# stm32-40.net
KiCad netlist of a schematic drawn in EAGLE
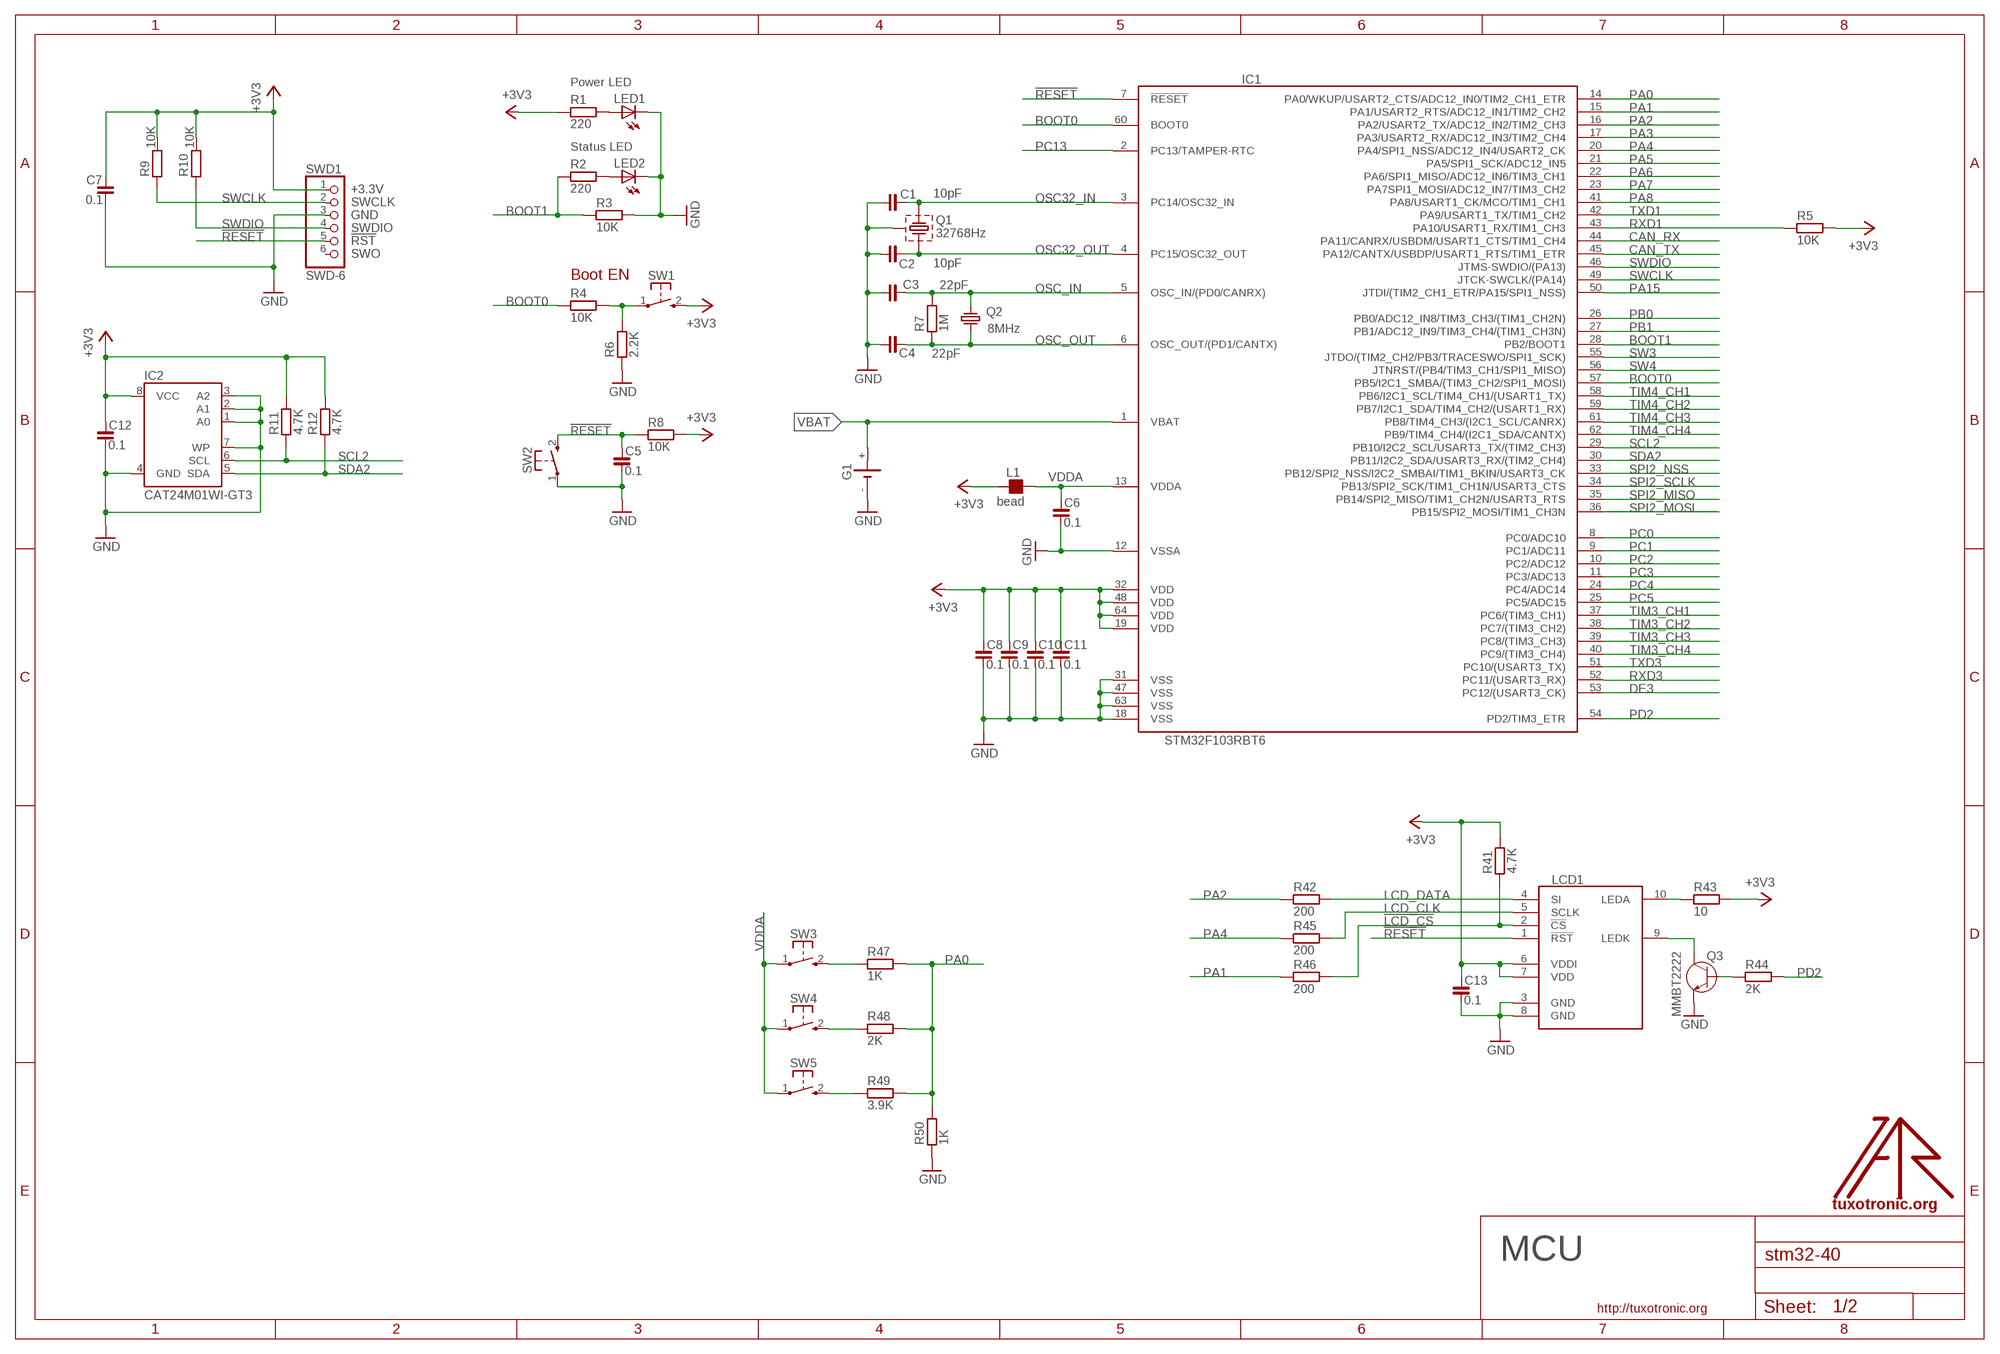
[diagram p0: schematic, sheet 1]
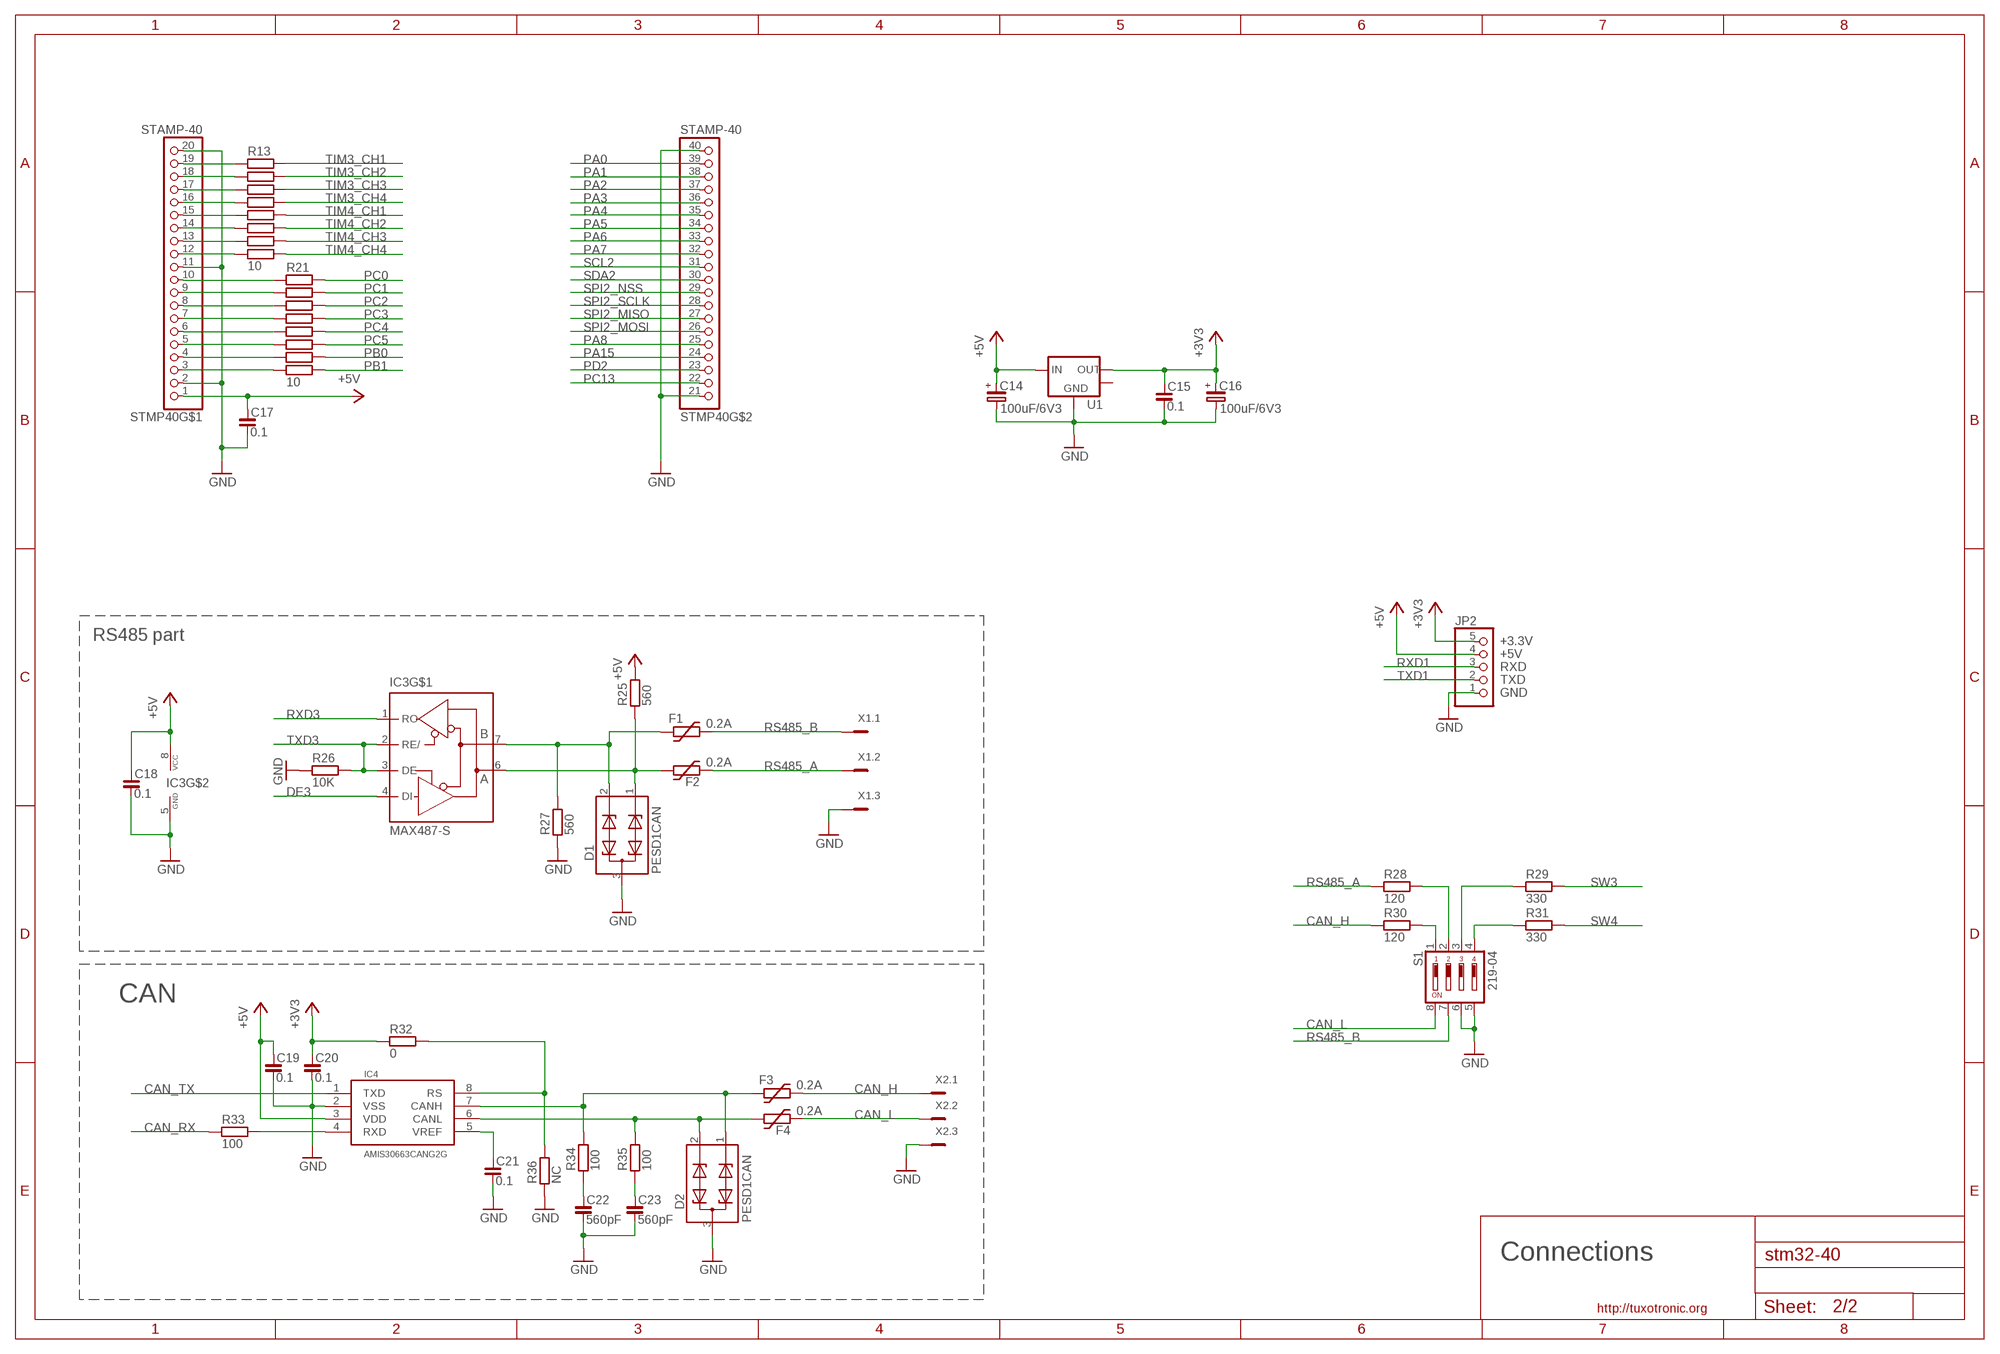
[diagram p1: schematic, sheet 2]

(export (version "E")
  (design (tool "Eeschema 10.0.6"))
  (components
    (comp (ref "C1")
      (value "10pF")
      (footprint "eagle-import:C0603")
      (libsource (lib "eagle-import") (part "C_0603"))
    )
    (comp (ref "C2")
      (value "10pF")
      (footprint "eagle-import:C0603")
      (libsource (lib "eagle-import") (part "C_0603"))
    )
    (comp (ref "C3")
      (value "22pF")
      (footprint "eagle-import:C0603")
      (libsource (lib "eagle-import") (part "C_0603"))
    )
    (comp (ref "C4")
      (value "22pF")
      (footprint "eagle-import:C0603")
      (libsource (lib "eagle-import") (part "C_0603"))
    )
    (comp (ref "C5")
      (value "0.1")
      (footprint "eagle-import:C0603")
      (libsource (lib "eagle-import") (part "C_0603"))
    )
    (comp (ref "C6")
      (value "0.1")
      (footprint "eagle-import:C0603")
      (libsource (lib "eagle-import") (part "C_0603"))
    )
    (comp (ref "C7")
      (value "0.1")
      (footprint "eagle-import:C0603")
      (libsource (lib "eagle-import") (part "C_0603"))
    )
    (comp (ref "C8")
      (value "0.1")
      (footprint "eagle-import:C0603")
      (libsource (lib "eagle-import") (part "C_0603"))
    )
    (comp (ref "C9")
      (value "0.1")
      (footprint "eagle-import:C0603")
      (libsource (lib "eagle-import") (part "C_0603"))
    )
    (comp (ref "C10")
      (value "0.1")
      (footprint "eagle-import:C0603")
      (libsource (lib "eagle-import") (part "C_0603"))
    )
    (comp (ref "C11")
      (value "0.1")
      (footprint "eagle-import:C0603")
      (libsource (lib "eagle-import") (part "C_0603"))
    )
    (comp (ref "C12")
      (value "0.1")
      (footprint "eagle-import:C0603")
      (libsource (lib "eagle-import") (part "C_0603"))
    )
    (comp (ref "C13")
      (value "0.1")
      (footprint "eagle-import:C0603")
      (libsource (lib "eagle-import") (part "C_0603"))
    )
    (comp (ref "G1")
      (value "1220SMT")
      (footprint "eagle-import:SMT1220")
      (libsource (lib "eagle-import") (part "1220SMT"))
    )
    (comp (ref "IC1")
      (value "STM32F103RBT6")
      (footprint "eagle-import:TQFP64")
      (libsource (lib "eagle-import") (part "STM32F103R"))
    )
    (comp (ref "IC2")
      (value "CAT24M01WI-GT3")
      (footprint "eagle-import:SO08")
      (libsource (lib "eagle-import") (part "AT24CS256"))
    )
    (comp (ref "L1")
      (value "bead")
      (footprint "eagle-import:L0603")
      (libsource (lib "eagle-import") (part "FB_0603"))
    )
    (comp (ref "LCD1")
      (value "LCD1202-EXT")
      (footprint "eagle-import:NOKIA1202LCD-EXT")
      (libsource (lib "eagle-import") (part "LCD1202-EXT"))
    )
    (comp (ref "LED1")
      (value "LEDCHIP-LED0805")
      (footprint "eagle-import:CHIP-LED0805")
      (libsource (lib "eagle-import") (part "LEDCHIP-LED0805"))
    )
    (comp (ref "LED2")
      (value "LEDCHIP-LED0805")
      (footprint "eagle-import:CHIP-LED0805")
      (libsource (lib "eagle-import") (part "LEDCHIP-LED0805"))
    )
    (comp (ref "Q1")
      (value "32768Hz")
      (footprint "eagle-import:TC38H-G")
      (libsource (lib "eagle-import") (part "CRSTL3-"))
    )
    (comp (ref "Q2")
      (value "8MHz")
      (footprint "eagle-import:HC49_S")
      (libsource (lib "eagle-import") (part "CRYSTAL-HC49S"))
    )
    (comp (ref "Q3")
      (value "MMBT2222")
      (footprint "eagle-import:SOT23")
      (libsource (lib "eagle-import") (part "MMBT2222"))
    )
    (comp (ref "R1")
      (value "220")
      (footprint "eagle-import:R0603")
      (libsource (lib "eagle-import") (part "R_0603"))
    )
    (comp (ref "R2")
      (value "220")
      (footprint "eagle-import:R0603")
      (libsource (lib "eagle-import") (part "R_0603"))
    )
    (comp (ref "R3")
      (value "10K")
      (footprint "eagle-import:R0603")
      (libsource (lib "eagle-import") (part "R_0603"))
    )
    (comp (ref "R4")
      (value "10K")
      (footprint "eagle-import:R0603")
      (libsource (lib "eagle-import") (part "R_0603"))
    )
    (comp (ref "R5")
      (value "10K")
      (footprint "eagle-import:R0603")
      (libsource (lib "eagle-import") (part "R_0603"))
    )
    (comp (ref "R6")
      (value "2.2K")
      (footprint "eagle-import:R0603")
      (libsource (lib "eagle-import") (part "R_0603"))
    )
    (comp (ref "R7")
      (value "1M")
      (footprint "eagle-import:R0603")
      (libsource (lib "eagle-import") (part "R_0603"))
    )
    (comp (ref "R8")
      (value "10K")
      (footprint "eagle-import:R0603")
      (libsource (lib "eagle-import") (part "R_0603"))
    )
    (comp (ref "R9")
      (value "10K")
      (footprint "eagle-import:R0603")
      (libsource (lib "eagle-import") (part "R_0603"))
    )
    (comp (ref "R10")
      (value "10K")
      (footprint "eagle-import:R0603")
      (libsource (lib "eagle-import") (part "R_0603"))
    )
    (comp (ref "R11")
      (value "4.7K")
      (footprint "eagle-import:R0603")
      (libsource (lib "eagle-import") (part "R_0603"))
    )
    (comp (ref "R12")
      (value "4.7K")
      (footprint "eagle-import:R0603")
      (libsource (lib "eagle-import") (part "R_0603"))
    )
    (comp (ref "R41")
      (value "4.7K")
      (footprint "eagle-import:R0603")
      (libsource (lib "eagle-import") (part "R_0603"))
    )
    (comp (ref "R42")
      (value "200")
      (footprint "eagle-import:R0603")
      (libsource (lib "eagle-import") (part "R_0603"))
    )
    (comp (ref "R43")
      (value "10")
      (footprint "eagle-import:R0603")
      (libsource (lib "eagle-import") (part "R_0603"))
    )
    (comp (ref "R44")
      (value "2K")
      (footprint "eagle-import:R0603")
      (libsource (lib "eagle-import") (part "R_0603"))
    )
    (comp (ref "R45")
      (value "200")
      (footprint "eagle-import:R0603")
      (libsource (lib "eagle-import") (part "R_0603"))
    )
    (comp (ref "R46")
      (value "200")
      (footprint "eagle-import:R0603")
      (libsource (lib "eagle-import") (part "R_0603"))
    )
    (comp (ref "R47")
      (value "1K")
      (footprint "eagle-import:R0603")
      (libsource (lib "eagle-import") (part "R_0603"))
    )
    (comp (ref "R48")
      (value "2K")
      (footprint "eagle-import:R0603")
      (libsource (lib "eagle-import") (part "R_0603"))
    )
    (comp (ref "R49")
      (value "3.9K")
      (footprint "eagle-import:R0603")
      (libsource (lib "eagle-import") (part "R_0603"))
    )
    (comp (ref "R50")
      (value "1K")
      (footprint "eagle-import:R0603")
      (libsource (lib "eagle-import") (part "R_0603"))
    )
    (comp (ref "SW1")
      (value "KSS-2EG4430")
      (footprint "eagle-import:KSS-2EG4430")
      (libsource (lib "eagle-import") (part "KSS-2EG4430"))
    )
    (comp (ref "SW2")
      (value "KSS-2EG4430")
      (footprint "eagle-import:KSS-2EG4430")
      (libsource (lib "eagle-import") (part "KSS-2EG4430"))
    )
    (comp (ref "SW3")
      (value "KSS-2EG4430")
      (footprint "eagle-import:KSS-2EG4430")
      (libsource (lib "eagle-import") (part "KSS-2EG4430"))
    )
    (comp (ref "SW4")
      (value "KSS-2EG4430")
      (footprint "eagle-import:KSS-2EG4430")
      (libsource (lib "eagle-import") (part "KSS-2EG4430"))
    )
    (comp (ref "SW5")
      (value "KSS-2EG4430")
      (footprint "eagle-import:KSS-2EG4430")
      (libsource (lib "eagle-import") (part "KSS-2EG4430"))
    )
    (comp (ref "SWD1")
      (value "SWD-6")
      (footprint "eagle-import:JTAG6PIN")
      (libsource (lib "eagle-import") (part "SWD-6"))
    )
    (comp (ref "U$1")
      (value "LOGO")
      (footprint "eagle-import:TT_LOGO")
      (libsource (lib "eagle-import") (part "LOGO"))
    )
    (comp (ref "C14")
      (value "100uF/6V3")
      (footprint "eagle-import:SMC_D")
      (libsource (lib "eagle-import") (part "CP_SMCD"))
    )
    (comp (ref "C15")
      (value "0.1")
      (footprint "eagle-import:C0805")
      (libsource (lib "eagle-import") (part "C_0805"))
    )
    (comp (ref "C16")
      (value "100uF/6V3")
      (footprint "eagle-import:SMC_D")
      (libsource (lib "eagle-import") (part "CP_SMCD"))
    )
    (comp (ref "C17")
      (value "0.1")
      (footprint "eagle-import:C0805")
      (libsource (lib "eagle-import") (part "C_0805"))
    )
    (comp (ref "C18")
      (value "0.1")
      (footprint "eagle-import:C0603")
      (libsource (lib "eagle-import") (part "C_0603"))
    )
    (comp (ref "C19")
      (value "0.1")
      (footprint "eagle-import:C0603")
      (libsource (lib "eagle-import") (part "C_0603"))
    )
    (comp (ref "C20")
      (value "0.1")
      (footprint "eagle-import:C0603")
      (libsource (lib "eagle-import") (part "C_0603"))
    )
    (comp (ref "C21")
      (value "0.1")
      (footprint "eagle-import:C0603")
      (libsource (lib "eagle-import") (part "C_0603"))
    )
    (comp (ref "C22")
      (value "560pF")
      (footprint "eagle-import:C0603")
      (libsource (lib "eagle-import") (part "C_0603"))
    )
    (comp (ref "C23")
      (value "560pF")
      (footprint "eagle-import:C0603")
      (libsource (lib "eagle-import") (part "C_0603"))
    )
    (comp (ref "D1")
      (value "PESD1CAN")
      (footprint "eagle-import:SOT23")
      (libsource (lib "eagle-import") (part "PESD1CAN"))
    )
    (comp (ref "D2")
      (value "PESD1CAN")
      (footprint "eagle-import:SOT23")
      (libsource (lib "eagle-import") (part "PESD1CAN"))
    )
    (comp (ref "F1")
      (value "0.2A")
      (footprint "eagle-import:1206L")
      (libsource (lib "eagle-import") (part "1206L"))
    )
    (comp (ref "F2")
      (value "0.2A")
      (footprint "eagle-import:1206L")
      (libsource (lib "eagle-import") (part "1206L"))
    )
    (comp (ref "F3")
      (value "0.2A")
      (footprint "eagle-import:1206L")
      (libsource (lib "eagle-import") (part "1206L"))
    )
    (comp (ref "F4")
      (value "0.2A")
      (footprint "eagle-import:1206L")
      (libsource (lib "eagle-import") (part "1206L"))
    )
    (comp (ref "IC3")
      (value "MAX487-S")
      (footprint "eagle-import:SO08")
      (libsource (lib "eagle-import") (part "MAX487-S"))
    )
    (comp (ref "IC4")
      (value "AMIS30663CANG2G")
      (footprint "eagle-import:SO08")
      (libsource (lib "eagle-import") (part "SN65HVD230"))
    )
    (comp (ref "JP2")
      (value "UART-5_2.54")
      (footprint "eagle-import:UART_1X05")
      (libsource (lib "eagle-import") (part "UART-5_2.54"))
    )
    (comp (ref "R13")
      (value "10")
      (footprint "eagle-import:R0603")
      (libsource (lib "eagle-import") (part "R_0603"))
    )
    (comp (ref "R14")
      (value "10")
      (footprint "eagle-import:R0603")
      (libsource (lib "eagle-import") (part "R_0603"))
    )
    (comp (ref "R15")
      (value "10")
      (footprint "eagle-import:R0603")
      (libsource (lib "eagle-import") (part "R_0603"))
    )
    (comp (ref "R16")
      (value "10")
      (footprint "eagle-import:R0603")
      (libsource (lib "eagle-import") (part "R_0603"))
    )
    (comp (ref "R17")
      (value "10")
      (footprint "eagle-import:R0603")
      (libsource (lib "eagle-import") (part "R_0603"))
    )
    (comp (ref "R18")
      (value "10")
      (footprint "eagle-import:R0603")
      (libsource (lib "eagle-import") (part "R_0603"))
    )
    (comp (ref "R19")
      (value "10")
      (footprint "eagle-import:R0603")
      (libsource (lib "eagle-import") (part "R_0603"))
    )
    (comp (ref "R20")
      (value "10")
      (footprint "eagle-import:R0603")
      (libsource (lib "eagle-import") (part "R_0603"))
    )
    (comp (ref "R21")
      (value "10")
      (footprint "eagle-import:R0603")
      (libsource (lib "eagle-import") (part "R_0603"))
    )
    (comp (ref "R22")
      (value "10")
      (footprint "eagle-import:R0603")
      (libsource (lib "eagle-import") (part "R_0603"))
    )
    (comp (ref "R23")
      (value "10")
      (footprint "eagle-import:R0603")
      (libsource (lib "eagle-import") (part "R_0603"))
    )
    (comp (ref "R24")
      (value "10")
      (footprint "eagle-import:R0603")
      (libsource (lib "eagle-import") (part "R_0603"))
    )
    (comp (ref "R25")
      (value "560")
      (footprint "eagle-import:R0603")
      (libsource (lib "eagle-import") (part "R_0603"))
    )
    (comp (ref "R26")
      (value "10K")
      (footprint "eagle-import:R0603")
      (libsource (lib "eagle-import") (part "R_0603"))
    )
    (comp (ref "R27")
      (value "560")
      (footprint "eagle-import:R0603")
      (libsource (lib "eagle-import") (part "R_0603"))
    )
    (comp (ref "R28")
      (value "120")
      (footprint "eagle-import:R0805")
      (libsource (lib "eagle-import") (part "R_0805"))
    )
    (comp (ref "R29")
      (value "330")
      (footprint "eagle-import:R0603")
      (libsource (lib "eagle-import") (part "R_0603"))
    )
    (comp (ref "R30")
      (value "120")
      (footprint "eagle-import:R0805")
      (libsource (lib "eagle-import") (part "R_0805"))
    )
    (comp (ref "R31")
      (value "330")
      (footprint "eagle-import:R0603")
      (libsource (lib "eagle-import") (part "R_0603"))
    )
    (comp (ref "R32")
      (value "0")
      (footprint "eagle-import:R0603")
      (libsource (lib "eagle-import") (part "R_0603"))
    )
    (comp (ref "R33")
      (value "100")
      (footprint "eagle-import:R0603")
      (libsource (lib "eagle-import") (part "R_0603"))
    )
    (comp (ref "R34")
      (value "100")
      (footprint "eagle-import:R0603")
      (libsource (lib "eagle-import") (part "R_0603"))
    )
    (comp (ref "R35")
      (value "100")
      (footprint "eagle-import:R0603")
      (libsource (lib "eagle-import") (part "R_0603"))
    )
    (comp (ref "R36")
      (value "NC")
      (footprint "eagle-import:R0603")
      (libsource (lib "eagle-import") (part "R_0603"))
    )
    (comp (ref "R37")
      (value "10")
      (footprint "eagle-import:R0603")
      (libsource (lib "eagle-import") (part "R_0603"))
    )
    (comp (ref "R38")
      (value "10")
      (footprint "eagle-import:R0603")
      (libsource (lib "eagle-import") (part "R_0603"))
    )
    (comp (ref "R39")
      (value "10")
      (footprint "eagle-import:R0603")
      (libsource (lib "eagle-import") (part "R_0603"))
    )
    (comp (ref "R40")
      (value "10")
      (footprint "eagle-import:R0603")
      (libsource (lib "eagle-import") (part "R_0603"))
    )
    (comp (ref "S1")
      (value "219-04")
      (footprint "eagle-import:CTS-219-04")
      (libsource (lib "eagle-import") (part "219-04"))
    )
    (comp (ref "STMP40")
      (value "STAMP-40")
      (footprint "eagle-import:STAMP-40")
      (libsource (lib "eagle-import") (part "STAMP-40"))
    )
    (comp (ref "U1")
      (value "LM1117-3.3")
      (footprint "eagle-import:SOT223")
      (libsource (lib "eagle-import") (part "LM1117-3.3"))
    )
    (comp (ref "X1")
      (value "MCV3")
      (footprint "eagle-import:MCV3")
      (libsource (lib "eagle-import") (part "MCV3"))
    )
    (comp (ref "X2")
      (value "MCV3")
      (footprint "eagle-import:MCV3")
      (libsource (lib "eagle-import") (part "MCV3"))
    )
  )
  (nets
    (net (code "1") (name "+3V3") (class "Default")
      (node (ref "C10") (pin "1") (pinfunction "1_1") (pintype "passive"))
      (node (ref "C11") (pin "1") (pinfunction "1_1") (pintype "passive"))
      (node (ref "C12") (pin "1") (pinfunction "1_1") (pintype "passive"))
      (node (ref "C13") (pin "1") (pinfunction "1_1") (pintype "passive"))
      (node (ref "C15") (pin "1") (pinfunction "1_1") (pintype "passive"))
      (node (ref "C16") (pin "+") (pinfunction "+_+") (pintype "passive"))
      (node (ref "C20") (pin "1") (pinfunction "1_1") (pintype "passive"))
      (node (ref "C7") (pin "1") (pinfunction "1_1") (pintype "passive"))
      (node (ref "C8") (pin "1") (pinfunction "1_1") (pintype "passive"))
      (node (ref "C9") (pin "1") (pinfunction "1_1") (pintype "passive"))
      (node (ref "IC1") (pin "19") (pinfunction "VDD_19") (pintype "power_in"))
      (node (ref "IC1") (pin "32") (pinfunction "VDD_32") (pintype "power_in"))
      (node (ref "IC1") (pin "48") (pinfunction "VDD_48") (pintype "power_in"))
      (node (ref "IC1") (pin "64") (pinfunction "VDD_64") (pintype "power_in"))
      (node (ref "IC2") (pin "8") (pinfunction "VCC_8") (pintype "power_in"))
      (node (ref "JP2") (pin "5") (pinfunction "5_5") (pintype "passive"))
      (node (ref "L1") (pin "1") (pinfunction "1_1") (pintype "passive"))
      (node (ref "LCD1") (pin "6") (pinfunction "VDDI_6") (pintype "power_in"))
      (node (ref "LCD1") (pin "7") (pinfunction "VDD_7") (pintype "power_in"))
      (node (ref "R1") (pin "1") (pinfunction "1_1") (pintype "passive"))
      (node (ref "R10") (pin "2") (pinfunction "2_2") (pintype "passive"))
      (node (ref "R11") (pin "2") (pinfunction "2_2") (pintype "passive"))
      (node (ref "R12") (pin "2") (pinfunction "2_2") (pintype "passive"))
      (node (ref "R32") (pin "1") (pinfunction "1_1") (pintype "passive"))
      (node (ref "R41") (pin "2") (pinfunction "2_2") (pintype "passive"))
      (node (ref "R43") (pin "2") (pinfunction "2_2") (pintype "passive"))
      (node (ref "R5") (pin "2") (pinfunction "2_2") (pintype "passive"))
      (node (ref "R8") (pin "2") (pinfunction "2_2") (pintype "passive"))
      (node (ref "R9") (pin "2") (pinfunction "2_2") (pintype "passive"))
      (node (ref "SW1") (pin "2") (pinfunction "S_2") (pintype "passive"))
      (node (ref "SWD1") (pin "1") (pinfunction "1_1") (pintype "passive"))
      (node (ref "U1") (pin "2") (pinfunction "OUT_2") (pintype "power_in"))
    )
    (net (code "2") (name "+5V") (class "Default")
      (node (ref "C14") (pin "+") (pinfunction "+_+") (pintype "passive"))
      (node (ref "C17") (pin "1") (pinfunction "1_1") (pintype "passive"))
      (node (ref "C18") (pin "1") (pinfunction "1_1") (pintype "passive"))
      (node (ref "C19") (pin "1") (pinfunction "1_1") (pintype "passive"))
      (node (ref "IC3") (pin "8") (pinfunction "VCC_8") (pintype "power_in"))
      (node (ref "IC4") (pin "3") (pinfunction "VDD_3") (pintype "power_in"))
      (node (ref "JP2") (pin "4") (pinfunction "4_4") (pintype "passive"))
      (node (ref "R25") (pin "2") (pinfunction "2_2") (pintype "passive"))
      (node (ref "STMP40") (pin "1") (pinfunction "1_1") (pintype "passive"))
      (node (ref "U1") (pin "3") (pinfunction "IN_3") (pintype "power_in"))
    )
    (net (code "3") (name "BOOT0") (class "Default")
      (node (ref "IC1") (pin "57") (pinfunction "PB5/I2C1_SMBA/(TIM3_CH2/SPI1_MOSI)_57") (pintype "bidirectional"))
      (node (ref "IC1") (pin "60") (pinfunction "BOOT0_60") (pintype "input"))
      (node (ref "R4") (pin "1") (pinfunction "1_1") (pintype "passive"))
    )
    (net (code "4") (name "BOOT1") (class "Default")
      (node (ref "IC1") (pin "28") (pinfunction "PB2/BOOT1_28") (pintype "bidirectional"))
      (node (ref "R2") (pin "1") (pinfunction "1_1") (pintype "passive"))
      (node (ref "R3") (pin "1") (pinfunction "1_1") (pintype "passive"))
    )
    (net (code "5") (name "CAN_H") (class "Default")
      (node (ref "F3") (pin "P$2") (pinfunction "2_P$2") (pintype "passive"))
      (node (ref "R30") (pin "1") (pinfunction "1_1") (pintype "passive"))
      (node (ref "X2") (pin "1") (pinfunction "SK_1") (pintype "passive"))
    )
    (net (code "6") (name "CAN_L") (class "Default")
      (node (ref "F4") (pin "P$2") (pinfunction "2_P$2") (pintype "passive"))
      (node (ref "S1") (pin "8") (pinfunction "8_8") (pintype "passive"))
      (node (ref "X2") (pin "2") (pinfunction "SK_2") (pintype "passive"))
    )
    (net (code "7") (name "CAN_RX") (class "Default")
      (node (ref "IC1") (pin "44") (pinfunction "PA11/CANRX/USBDM/USART1_CTS/TIM1_CH4_44") (pintype "bidirectional"))
      (node (ref "R33") (pin "1") (pinfunction "1_1") (pintype "passive"))
    )
    (net (code "8") (name "CAN_TX") (class "Default")
      (node (ref "IC1") (pin "45") (pinfunction "PA12/CANTX/USBDP/USART1_RTS/TIM1_ETR_45") (pintype "bidirectional"))
      (node (ref "IC4") (pin "1") (pinfunction "TXD_1") (pintype "input"))
    )
    (net (code "9") (name "DE3") (class "Default")
      (node (ref "IC1") (pin "53") (pinfunction "PC12/(USART3_CK)_53") (pintype "bidirectional"))
      (node (ref "IC3") (pin "4") (pinfunction "DI_4") (pintype "input"))
    )
    (net (code "10") (name "GND") (class "Default")
      (node (ref "C1") (pin "2") (pinfunction "2_2") (pintype "passive"))
      (node (ref "C10") (pin "2") (pinfunction "2_2") (pintype "passive"))
      (node (ref "C11") (pin "2") (pinfunction "2_2") (pintype "passive"))
      (node (ref "C12") (pin "2") (pinfunction "2_2") (pintype "passive"))
      (node (ref "C13") (pin "2") (pinfunction "2_2") (pintype "passive"))
      (node (ref "C14") (pin "-") (pinfunction "-_-") (pintype "passive"))
      (node (ref "C15") (pin "2") (pinfunction "2_2") (pintype "passive"))
      (node (ref "C16") (pin "-") (pinfunction "-_-") (pintype "passive"))
      (node (ref "C17") (pin "2") (pinfunction "2_2") (pintype "passive"))
      (node (ref "C18") (pin "2") (pinfunction "2_2") (pintype "passive"))
      (node (ref "C19") (pin "2") (pinfunction "2_2") (pintype "passive"))
      (node (ref "C2") (pin "2") (pinfunction "2_2") (pintype "passive"))
      (node (ref "C20") (pin "2") (pinfunction "2_2") (pintype "passive"))
      (node (ref "C21") (pin "2") (pinfunction "2_2") (pintype "passive"))
      (node (ref "C22") (pin "2") (pinfunction "2_2") (pintype "passive"))
      (node (ref "C23") (pin "2") (pinfunction "2_2") (pintype "passive"))
      (node (ref "C3") (pin "2") (pinfunction "2_2") (pintype "passive"))
      (node (ref "C4") (pin "2") (pinfunction "2_2") (pintype "passive"))
      (node (ref "C5") (pin "2") (pinfunction "2_2") (pintype "passive"))
      (node (ref "C6") (pin "2") (pinfunction "2_2") (pintype "passive"))
      (node (ref "C7") (pin "2") (pinfunction "2_2") (pintype "passive"))
      (node (ref "C8") (pin "2") (pinfunction "2_2") (pintype "passive"))
      (node (ref "C9") (pin "2") (pinfunction "2_2") (pintype "passive"))
      (node (ref "D1") (pin "3") (pinfunction "3_3") (pintype "passive"))
      (node (ref "D2") (pin "3") (pinfunction "3_3") (pintype "passive"))
      (node (ref "G1") (pin "-") (pinfunction "-_-") (pintype "passive"))
      (node (ref "IC1") (pin "12") (pinfunction "VSSA_12") (pintype "power_in"))
      (node (ref "IC1") (pin "18") (pinfunction "VSS_18") (pintype "power_in"))
      (node (ref "IC1") (pin "31") (pinfunction "VSS_31") (pintype "power_in"))
      (node (ref "IC1") (pin "47") (pinfunction "VSS_47") (pintype "power_in"))
      (node (ref "IC1") (pin "63") (pinfunction "VSS_63") (pintype "power_in"))
      (node (ref "IC2") (pin "1") (pinfunction "A0_1") (pintype "input"))
      (node (ref "IC2") (pin "2") (pinfunction "A1_2") (pintype "input"))
      (node (ref "IC2") (pin "3") (pinfunction "A2_3") (pintype "input"))
      (node (ref "IC2") (pin "4") (pinfunction "GND_4") (pintype "power_in"))
      (node (ref "IC2") (pin "7") (pinfunction "WP_7") (pintype "input"))
      (node (ref "IC3") (pin "5") (pinfunction "GND_5") (pintype "power_in"))
      (node (ref "IC4") (pin "2") (pinfunction "VSS_2") (pintype "power_in"))
      (node (ref "JP2") (pin "1") (pinfunction "1_1") (pintype "passive"))
      (node (ref "LCD1") (pin "3") (pinfunction "GND_3") (pintype "power_in"))
      (node (ref "LCD1") (pin "8") (pinfunction "GND_8") (pintype "power_in"))
      (node (ref "LED1") (pin "C") (pinfunction "C_C") (pintype "passive"))
      (node (ref "LED2") (pin "C") (pinfunction "C_C") (pintype "passive"))
      (node (ref "Q1") (pin "GND") (pinfunction "P$1_GND") (pintype "passive"))
      (node (ref "Q3") (pin "2") (pinfunction "E_2") (pintype "passive"))
      (node (ref "R26") (pin "1") (pinfunction "1_1") (pintype "passive"))
      (node (ref "R27") (pin "1") (pinfunction "1_1") (pintype "passive"))
      (node (ref "R3") (pin "2") (pinfunction "2_2") (pintype "passive"))
      (node (ref "R36") (pin "1") (pinfunction "1_1") (pintype "passive"))
      (node (ref "R50") (pin "1") (pinfunction "1_1") (pintype "passive"))
      (node (ref "R6") (pin "1") (pinfunction "1_1") (pintype "passive"))
      (node (ref "S1") (pin "5") (pinfunction "5_5") (pintype "passive"))
      (node (ref "S1") (pin "6") (pinfunction "6_6") (pintype "passive"))
      (node (ref "STMP40") (pin "11") (pinfunction "11_11") (pintype "passive"))
      (node (ref "STMP40") (pin "2") (pinfunction "2_2") (pintype "passive"))
      (node (ref "STMP40") (pin "20") (pinfunction "20_20") (pintype "passive"))
      (node (ref "STMP40") (pin "21") (pinfunction "1_21") (pintype "passive"))
      (node (ref "STMP40") (pin "40") (pinfunction "20_40") (pintype "passive"))
      (node (ref "SW2") (pin "1") (pinfunction "P_1") (pintype "passive"))
      (node (ref "SWD1") (pin "3") (pinfunction "3_3") (pintype "passive"))
      (node (ref "U1") (pin "1") (pinfunction "GND_1") (pintype "power_in"))
      (node (ref "X1") (pin "3") (pinfunction "SK_3") (pintype "passive"))
      (node (ref "X2") (pin "3") (pinfunction "SK_3") (pintype "passive"))
    )
    (net (code "11") (name "LCD_CLK") (class "Default")
      (node (ref "LCD1") (pin "5") (pinfunction "SCLK_5") (pintype "input"))
      (node (ref "R45") (pin "2") (pinfunction "2_2") (pintype "passive"))
    )
    (net (code "12") (name "LCD_DATA") (class "Default")
      (node (ref "LCD1") (pin "4") (pinfunction "SI_4") (pintype "input"))
      (node (ref "R42") (pin "2") (pinfunction "2_2") (pintype "passive"))
    )
    (net (code "13") (name "Net-(C22-Pad1)") (class "Default")
      (node (ref "C22") (pin "1") (pinfunction "1_1") (pintype "passive"))
      (node (ref "R34") (pin "1") (pinfunction "1_1") (pintype "passive"))
    )
    (net (code "14") (name "Net-(C23-Pad1)") (class "Default")
      (node (ref "C23") (pin "1") (pinfunction "1_1") (pintype "passive"))
      (node (ref "R35") (pin "1") (pinfunction "1_1") (pintype "passive"))
    )
    (net (code "15") (name "Net-(F1-1)") (class "Default")
      (node (ref "D1") (pin "2") (pinfunction "2_2") (pintype "passive"))
      (node (ref "F1") (pin "P$1") (pinfunction "1_P$1") (pintype "passive"))
      (node (ref "IC3") (pin "7") (pinfunction "B_7") (pintype "passive"))
      (node (ref "R27") (pin "2") (pinfunction "2_2") (pintype "passive"))
    )
    (net (code "16") (name "Net-(F2-1)") (class "Default")
      (node (ref "D1") (pin "1") (pinfunction "1_1") (pintype "passive"))
      (node (ref "F2") (pin "P$1") (pinfunction "1_P$1") (pintype "passive"))
      (node (ref "IC3") (pin "6") (pinfunction "A_6") (pintype "passive"))
      (node (ref "R25") (pin "1") (pinfunction "1_1") (pintype "passive"))
    )
    (net (code "17") (name "Net-(F3-1)") (class "Default")
      (node (ref "D2") (pin "1") (pinfunction "1_1") (pintype "passive"))
      (node (ref "F3") (pin "P$1") (pinfunction "1_P$1") (pintype "passive"))
      (node (ref "IC4") (pin "7") (pinfunction "CANH_7") (pintype "bidirectional"))
      (node (ref "R34") (pin "2") (pinfunction "2_2") (pintype "passive"))
    )
    (net (code "18") (name "Net-(F4-1)") (class "Default")
      (node (ref "D2") (pin "2") (pinfunction "2_2") (pintype "passive"))
      (node (ref "F4") (pin "P$1") (pinfunction "1_P$1") (pintype "passive"))
      (node (ref "IC4") (pin "6") (pinfunction "CANL_6") (pintype "bidirectional"))
      (node (ref "R35") (pin "2") (pinfunction "2_2") (pintype "passive"))
    )
    (net (code "19") (name "Net-(IC4-RS)") (class "Default")
      (node (ref "IC4") (pin "8") (pinfunction "RS_8") (pintype "input"))
      (node (ref "R32") (pin "2") (pinfunction "2_2") (pintype "passive"))
      (node (ref "R36") (pin "2") (pinfunction "2_2") (pintype "passive"))
    )
    (net (code "20") (name "Net-(IC4-RXD)") (class "Default")
      (node (ref "IC4") (pin "4") (pinfunction "RXD_4") (pintype "output"))
      (node (ref "R33") (pin "2") (pinfunction "2_2") (pintype "passive"))
    )
    (net (code "21") (name "Net-(IC4-VREF)") (class "Default")
      (node (ref "C21") (pin "1") (pinfunction "1_1") (pintype "passive"))
      (node (ref "IC4") (pin "5") (pinfunction "VREF_5") (pintype "passive"))
    )
    (net (code "22") (name "Net-(LCD1-LEDA)") (class "Default")
      (node (ref "LCD1") (pin "10") (pinfunction "LEDA_10") (pintype "passive"))
      (node (ref "R43") (pin "1") (pinfunction "1_1") (pintype "passive"))
    )
    (net (code "23") (name "Net-(LCD1-LEDK)") (class "Default")
      (node (ref "LCD1") (pin "9") (pinfunction "LEDK_9") (pintype "passive"))
      (node (ref "Q3") (pin "3") (pinfunction "C_3") (pintype "passive"))
    )
    (net (code "24") (name "Net-(LED1-PadA)") (class "Default")
      (node (ref "LED1") (pin "A") (pinfunction "A_A") (pintype "passive"))
      (node (ref "R1") (pin "2") (pinfunction "2_2") (pintype "passive"))
    )
    (net (code "25") (name "Net-(LED2-PadA)") (class "Default")
      (node (ref "LED2") (pin "A") (pinfunction "A_A") (pintype "passive"))
      (node (ref "R2") (pin "2") (pinfunction "2_2") (pintype "passive"))
    )
    (net (code "26") (name "Net-(Q3-B)") (class "Default")
      (node (ref "Q3") (pin "1") (pinfunction "B_1") (pintype "passive"))
      (node (ref "R44") (pin "1") (pinfunction "1_1") (pintype "passive"))
    )
    (net (code "27") (name "Net-(R13-Pad1)") (class "Default")
      (node (ref "R13") (pin "1") (pinfunction "1_1") (pintype "passive"))
      (node (ref "STMP40") (pin "19") (pinfunction "19_19") (pintype "passive"))
    )
    (net (code "28") (name "Net-(R14-Pad1)") (class "Default")
      (node (ref "R14") (pin "1") (pinfunction "1_1") (pintype "passive"))
      (node (ref "STMP40") (pin "18") (pinfunction "18_18") (pintype "passive"))
    )
    (net (code "29") (name "Net-(R15-Pad1)") (class "Default")
      (node (ref "R15") (pin "1") (pinfunction "1_1") (pintype "passive"))
      (node (ref "STMP40") (pin "17") (pinfunction "17_17") (pintype "passive"))
    )
    (net (code "30") (name "Net-(R16-Pad1)") (class "Default")
      (node (ref "R16") (pin "1") (pinfunction "1_1") (pintype "passive"))
      (node (ref "STMP40") (pin "16") (pinfunction "16_16") (pintype "passive"))
    )
    (net (code "31") (name "Net-(R17-Pad1)") (class "Default")
      (node (ref "R17") (pin "1") (pinfunction "1_1") (pintype "passive"))
      (node (ref "STMP40") (pin "15") (pinfunction "15_15") (pintype "passive"))
    )
    (net (code "32") (name "Net-(R18-Pad1)") (class "Default")
      (node (ref "R18") (pin "1") (pinfunction "1_1") (pintype "passive"))
      (node (ref "STMP40") (pin "14") (pinfunction "14_14") (pintype "passive"))
    )
    (net (code "33") (name "Net-(R19-Pad1)") (class "Default")
      (node (ref "R19") (pin "1") (pinfunction "1_1") (pintype "passive"))
      (node (ref "STMP40") (pin "13") (pinfunction "13_13") (pintype "passive"))
    )
    (net (code "34") (name "Net-(R20-Pad1)") (class "Default")
      (node (ref "R20") (pin "1") (pinfunction "1_1") (pintype "passive"))
      (node (ref "STMP40") (pin "12") (pinfunction "12_12") (pintype "passive"))
    )
    (net (code "35") (name "Net-(R21-Pad1)") (class "Default")
      (node (ref "R21") (pin "1") (pinfunction "1_1") (pintype "passive"))
      (node (ref "STMP40") (pin "10") (pinfunction "10_10") (pintype "passive"))
    )
    (net (code "36") (name "Net-(R22-Pad1)") (class "Default")
      (node (ref "R22") (pin "1") (pinfunction "1_1") (pintype "passive"))
      (node (ref "STMP40") (pin "9") (pinfunction "9_9") (pintype "passive"))
    )
    (net (code "37") (name "Net-(R23-Pad1)") (class "Default")
      (node (ref "R23") (pin "1") (pinfunction "1_1") (pintype "passive"))
      (node (ref "STMP40") (pin "8") (pinfunction "8_8") (pintype "passive"))
    )
    (net (code "38") (name "Net-(R24-Pad1)") (class "Default")
      (node (ref "R24") (pin "1") (pinfunction "1_1") (pintype "passive"))
      (node (ref "STMP40") (pin "7") (pinfunction "7_7") (pintype "passive"))
    )
    (net (code "39") (name "Net-(R28-Pad2)") (class "Default")
      (node (ref "R28") (pin "2") (pinfunction "2_2") (pintype "passive"))
      (node (ref "S1") (pin "2") (pinfunction "2_2") (pintype "passive"))
    )
    (net (code "40") (name "Net-(R29-Pad1)") (class "Default")
      (node (ref "R29") (pin "1") (pinfunction "1_1") (pintype "passive"))
      (node (ref "S1") (pin "3") (pinfunction "3_3") (pintype "passive"))
    )
    (net (code "41") (name "Net-(R30-Pad2)") (class "Default")
      (node (ref "R30") (pin "2") (pinfunction "2_2") (pintype "passive"))
      (node (ref "S1") (pin "1") (pinfunction "1_1") (pintype "passive"))
    )
    (net (code "42") (name "Net-(R31-Pad1)") (class "Default")
      (node (ref "R31") (pin "1") (pinfunction "1_1") (pintype "passive"))
      (node (ref "S1") (pin "4") (pinfunction "4_4") (pintype "passive"))
    )
    (net (code "43") (name "Net-(R37-Pad1)") (class "Default")
      (node (ref "R37") (pin "1") (pinfunction "1_1") (pintype "passive"))
      (node (ref "STMP40") (pin "6") (pinfunction "6_6") (pintype "passive"))
    )
    (net (code "44") (name "Net-(R38-Pad1)") (class "Default")
      (node (ref "R38") (pin "1") (pinfunction "1_1") (pintype "passive"))
      (node (ref "STMP40") (pin "5") (pinfunction "5_5") (pintype "passive"))
    )
    (net (code "45") (name "Net-(R39-Pad1)") (class "Default")
      (node (ref "R39") (pin "1") (pinfunction "1_1") (pintype "passive"))
      (node (ref "STMP40") (pin "4") (pinfunction "4_4") (pintype "passive"))
    )
    (net (code "46") (name "Net-(R40-Pad1)") (class "Default")
      (node (ref "R40") (pin "1") (pinfunction "1_1") (pintype "passive"))
      (node (ref "STMP40") (pin "3") (pinfunction "3_3") (pintype "passive"))
    )
    (net (code "47") (name "Net-(SW1-P)") (class "Default")
      (node (ref "R4") (pin "2") (pinfunction "2_2") (pintype "passive"))
      (node (ref "R6") (pin "2") (pinfunction "2_2") (pintype "passive"))
      (node (ref "SW1") (pin "1") (pinfunction "P_1") (pintype "passive"))
    )
    (net (code "48") (name "Net-(SW3-S)") (class "Default")
      (node (ref "R47") (pin "1") (pinfunction "1_1") (pintype "passive"))
      (node (ref "SW3") (pin "2") (pinfunction "S_2") (pintype "passive"))
    )
    (net (code "49") (name "Net-(SW4-S)") (class "Default")
      (node (ref "R48") (pin "1") (pinfunction "1_1") (pintype "passive"))
      (node (ref "SW4") (pin "2") (pinfunction "S_2") (pintype "passive"))
    )
    (net (code "50") (name "Net-(SW5-S)") (class "Default")
      (node (ref "R49") (pin "1") (pinfunction "1_1") (pintype "passive"))
      (node (ref "SW5") (pin "2") (pinfunction "S_2") (pintype "passive"))
    )
    (net (code "51") (name "OSC32_IN") (class "Default")
      (node (ref "C1") (pin "1") (pinfunction "1_1") (pintype "passive"))
      (node (ref "IC1") (pin "3") (pinfunction "PC14/OSC32_IN_3") (pintype "bidirectional"))
      (node (ref "Q1") (pin "2") (pinfunction "2_2") (pintype "passive"))
    )
    (net (code "52") (name "OSC32_OUT") (class "Default")
      (node (ref "C2") (pin "1") (pinfunction "1_1") (pintype "passive"))
      (node (ref "IC1") (pin "4") (pinfunction "PC15/OSC32_OUT_4") (pintype "bidirectional"))
      (node (ref "Q1") (pin "1") (pinfunction "1_1") (pintype "passive"))
    )
    (net (code "53") (name "OSC_IN") (class "Default")
      (node (ref "C3") (pin "1") (pinfunction "1_1") (pintype "passive"))
      (node (ref "IC1") (pin "5") (pinfunction "OSC_IN/(PD0/CANRX)_5") (pintype "input"))
      (node (ref "Q2") (pin "1") (pinfunction "1_1") (pintype "passive"))
      (node (ref "R7") (pin "2") (pinfunction "2_2") (pintype "passive"))
    )
    (net (code "54") (name "OSC_OUT") (class "Default")
      (node (ref "C4") (pin "1") (pinfunction "1_1") (pintype "passive"))
      (node (ref "IC1") (pin "6") (pinfunction "OSC_OUT/(PD1/CANTX)_6") (pintype "output"))
      (node (ref "Q2") (pin "2") (pinfunction "2_2") (pintype "passive"))
      (node (ref "R7") (pin "1") (pinfunction "1_1") (pintype "passive"))
    )
    (net (code "55") (name "PA0") (class "Default")
      (node (ref "IC1") (pin "14") (pinfunction "PA0/WKUP/USART2_CTS/ADC12_IN0/TIM2_CH1_ETR_14") (pintype "bidirectional"))
      (node (ref "R47") (pin "2") (pinfunction "2_2") (pintype "passive"))
      (node (ref "R48") (pin "2") (pinfunction "2_2") (pintype "passive"))
      (node (ref "R49") (pin "2") (pinfunction "2_2") (pintype "passive"))
      (node (ref "R50") (pin "2") (pinfunction "2_2") (pintype "passive"))
      (node (ref "STMP40") (pin "39") (pinfunction "19_39") (pintype "passive"))
    )
    (net (code "56") (name "PA1") (class "Default")
      (node (ref "IC1") (pin "15") (pinfunction "PA1/USART2_RTS/ADC12_IN1/TIM2_CH2_15") (pintype "bidirectional"))
      (node (ref "R46") (pin "1") (pinfunction "1_1") (pintype "passive"))
      (node (ref "STMP40") (pin "38") (pinfunction "18_38") (pintype "passive"))
    )
    (net (code "57") (name "PA2") (class "Default")
      (node (ref "IC1") (pin "16") (pinfunction "PA2/USART2_TX/ADC12_IN2/TIM2_CH3_16") (pintype "bidirectional"))
      (node (ref "R42") (pin "1") (pinfunction "1_1") (pintype "passive"))
      (node (ref "STMP40") (pin "37") (pinfunction "17_37") (pintype "passive"))
    )
    (net (code "58") (name "PA3") (class "Default")
      (node (ref "IC1") (pin "17") (pinfunction "PA3/USART2_RX/ADC12_IN3/TIM2_CH4_17") (pintype "bidirectional"))
      (node (ref "STMP40") (pin "36") (pinfunction "16_36") (pintype "passive"))
    )
    (net (code "59") (name "PA4") (class "Default")
      (node (ref "IC1") (pin "20") (pinfunction "PA4/SPI1_NSS/ADC12_IN4/USART2_CK_20") (pintype "bidirectional"))
      (node (ref "R45") (pin "1") (pinfunction "1_1") (pintype "passive"))
      (node (ref "STMP40") (pin "35") (pinfunction "15_35") (pintype "passive"))
    )
    (net (code "60") (name "PA5") (class "Default")
      (node (ref "IC1") (pin "21") (pinfunction "PA5/SPI1_SCK/ADC12_IN5_21") (pintype "bidirectional"))
      (node (ref "STMP40") (pin "34") (pinfunction "14_34") (pintype "passive"))
    )
    (net (code "61") (name "PA6") (class "Default")
      (node (ref "IC1") (pin "22") (pinfunction "PA6/SPI1_MISO/ADC12_IN6/TIM3_CH1_22") (pintype "bidirectional"))
      (node (ref "STMP40") (pin "33") (pinfunction "13_33") (pintype "passive"))
    )
    (net (code "62") (name "PA7") (class "Default")
      (node (ref "IC1") (pin "23") (pinfunction "PA7SPI1_MOSI/ADC12_IN7/TIM3_CH2_23") (pintype "bidirectional"))
      (node (ref "STMP40") (pin "32") (pinfunction "12_32") (pintype "passive"))
    )
    (net (code "63") (name "PA8") (class "Default")
      (node (ref "IC1") (pin "41") (pinfunction "PA8/USART1_CK/MCO/TIM1_CH1_41") (pintype "bidirectional"))
      (node (ref "STMP40") (pin "25") (pinfunction "5_25") (pintype "passive"))
    )
    (net (code "64") (name "PA15") (class "Default")
      (node (ref "IC1") (pin "50") (pinfunction "JTDI/(TIM2_CH1_ETR/PA15/SPI1_NSS)_50") (pintype "bidirectional"))
      (node (ref "STMP40") (pin "24") (pinfunction "4_24") (pintype "passive"))
    )
    (net (code "65") (name "PB0") (class "Default")
      (node (ref "IC1") (pin "26") (pinfunction "PB0/ADC12_IN8/TIM3_CH3/(TIM1_CH2N)_26") (pintype "bidirectional"))
      (node (ref "R39") (pin "2") (pinfunction "2_2") (pintype "passive"))
    )
    (net (code "66") (name "PB1") (class "Default")
      (node (ref "IC1") (pin "27") (pinfunction "PB1/ADC12_IN9/TIM3_CH4/(TIM1_CH3N)_27") (pintype "bidirectional"))
      (node (ref "R40") (pin "2") (pinfunction "2_2") (pintype "passive"))
    )
    (net (code "67") (name "PC0") (class "Default")
      (node (ref "IC1") (pin "8") (pinfunction "PC0/ADC10_8") (pintype "bidirectional"))
      (node (ref "R21") (pin "2") (pinfunction "2_2") (pintype "passive"))
    )
    (net (code "68") (name "PC1") (class "Default")
      (node (ref "IC1") (pin "9") (pinfunction "PC1/ADC11_9") (pintype "bidirectional"))
      (node (ref "R22") (pin "2") (pinfunction "2_2") (pintype "passive"))
    )
    (net (code "69") (name "PC2") (class "Default")
      (node (ref "IC1") (pin "10") (pinfunction "PC2/ADC12_10") (pintype "bidirectional"))
      (node (ref "R23") (pin "2") (pinfunction "2_2") (pintype "passive"))
    )
    (net (code "70") (name "PC3") (class "Default")
      (node (ref "IC1") (pin "11") (pinfunction "PC3/ADC13_11") (pintype "bidirectional"))
      (node (ref "R24") (pin "2") (pinfunction "2_2") (pintype "passive"))
    )
    (net (code "71") (name "PC4") (class "Default")
      (node (ref "IC1") (pin "24") (pinfunction "PC4/ADC14_24") (pintype "bidirectional"))
      (node (ref "R37") (pin "2") (pinfunction "2_2") (pintype "passive"))
    )
    (net (code "72") (name "PC5") (class "Default")
      (node (ref "IC1") (pin "25") (pinfunction "PC5/ADC15_25") (pintype "bidirectional"))
      (node (ref "R38") (pin "2") (pinfunction "2_2") (pintype "passive"))
    )
    (net (code "73") (name "PC13") (class "Default")
      (node (ref "IC1") (pin "2") (pinfunction "PC13/TAMPER-RTC_2") (pintype "bidirectional"))
      (node (ref "STMP40") (pin "22") (pinfunction "2_22") (pintype "passive"))
    )
    (net (code "74") (name "PD2") (class "Default")
      (node (ref "IC1") (pin "54") (pinfunction "PD2/TIM3_ETR_54") (pintype "bidirectional"))
      (node (ref "R44") (pin "2") (pinfunction "2_2") (pintype "passive"))
      (node (ref "STMP40") (pin "23") (pinfunction "3_23") (pintype "passive"))
    )
    (net (code "75") (name "RS485_A") (class "Default")
      (node (ref "F2") (pin "P$2") (pinfunction "2_P$2") (pintype "passive"))
      (node (ref "R28") (pin "1") (pinfunction "1_1") (pintype "passive"))
      (node (ref "X1") (pin "2") (pinfunction "SK_2") (pintype "passive"))
    )
    (net (code "76") (name "RS485_B") (class "Default")
      (node (ref "F1") (pin "P$2") (pinfunction "2_P$2") (pintype "passive"))
      (node (ref "S1") (pin "7") (pinfunction "7_7") (pintype "passive"))
      (node (ref "X1") (pin "1") (pinfunction "SK_1") (pintype "passive"))
    )
    (net (code "77") (name "RXD1") (class "Default")
      (node (ref "IC1") (pin "43") (pinfunction "PA10/USART1_RX/TIM1_CH3_43") (pintype "bidirectional"))
      (node (ref "JP2") (pin "3") (pinfunction "3_3") (pintype "passive"))
      (node (ref "R5") (pin "1") (pinfunction "1_1") (pintype "passive"))
    )
    (net (code "78") (name "RXD3") (class "Default")
      (node (ref "IC1") (pin "52") (pinfunction "PC11/(USART3_RX)_52") (pintype "bidirectional"))
      (node (ref "IC3") (pin "1") (pinfunction "RO_1") (pintype "output"))
    )
    (net (code "79") (name "SCL2") (class "Default")
      (node (ref "IC1") (pin "29") (pinfunction "PB10/I2C2_SCL/USART3_TX/(TIM2_CH3)_29") (pintype "bidirectional"))
      (node (ref "IC2") (pin "6") (pinfunction "SCL_6") (pintype "bidirectional"))
      (node (ref "R11") (pin "1") (pinfunction "1_1") (pintype "passive"))
      (node (ref "STMP40") (pin "31") (pinfunction "11_31") (pintype "passive"))
    )
    (net (code "80") (name "SDA2") (class "Default")
      (node (ref "IC1") (pin "30") (pinfunction "PB11/I2C2_SDA/USART3_RX/(TIM2_CH4)_30") (pintype "bidirectional"))
      (node (ref "IC2") (pin "5") (pinfunction "SDA_5") (pintype "bidirectional"))
      (node (ref "R12") (pin "1") (pinfunction "1_1") (pintype "passive"))
      (node (ref "STMP40") (pin "30") (pinfunction "10_30") (pintype "passive"))
    )
    (net (code "81") (name "SPI2_MISO") (class "Default")
      (node (ref "IC1") (pin "35") (pinfunction "PB14/SPI2_MISO/TIM1_CH2N/USART3_RTS_35") (pintype "bidirectional"))
      (node (ref "STMP40") (pin "27") (pinfunction "7_27") (pintype "passive"))
    )
    (net (code "82") (name "SPI2_MOSI") (class "Default")
      (node (ref "IC1") (pin "36") (pinfunction "PB15/SPI2_MOSI/TIM1_CH3N_36") (pintype "bidirectional"))
      (node (ref "STMP40") (pin "26") (pinfunction "6_26") (pintype "passive"))
    )
    (net (code "83") (name "SPI2_NSS") (class "Default")
      (node (ref "IC1") (pin "33") (pinfunction "PB12/SPI2_NSS/I2C2_SMBAI/TIM1_BKIN/USART3_CK_33") (pintype "bidirectional"))
      (node (ref "STMP40") (pin "29") (pinfunction "9_29") (pintype "passive"))
    )
    (net (code "84") (name "SPI2_SCLK") (class "Default")
      (node (ref "IC1") (pin "34") (pinfunction "PB13/SPI2_SCK/TIM1_CH1N/USART3_CTS_34") (pintype "bidirectional"))
      (node (ref "STMP40") (pin "28") (pinfunction "8_28") (pintype "passive"))
    )
    (net (code "85") (name "SW3") (class "Default")
      (node (ref "IC1") (pin "55") (pinfunction "JTDO/(TIM2_CH2/PB3/TRACESWO/SPI1_SCK)_55") (pintype "bidirectional"))
      (node (ref "R29") (pin "2") (pinfunction "2_2") (pintype "passive"))
    )
    (net (code "86") (name "SW4") (class "Default")
      (node (ref "IC1") (pin "56") (pinfunction "JTNRST/(PB4/TIM3_CH1/SPI1_MISO)_56") (pintype "bidirectional"))
      (node (ref "R31") (pin "2") (pinfunction "2_2") (pintype "passive"))
    )
    (net (code "87") (name "SWCLK") (class "Default")
      (node (ref "IC1") (pin "49") (pinfunction "JTCK-SWCLK/(PA14)_49") (pintype "bidirectional"))
      (node (ref "R9") (pin "1") (pinfunction "1_1") (pintype "passive"))
      (node (ref "SWD1") (pin "2") (pinfunction "2_2") (pintype "passive"))
    )
    (net (code "88") (name "SWDIO") (class "Default")
      (node (ref "IC1") (pin "46") (pinfunction "JTMS-SWDIO/(PA13)_46") (pintype "bidirectional"))
      (node (ref "R10") (pin "1") (pinfunction "1_1") (pintype "passive"))
      (node (ref "SWD1") (pin "4") (pinfunction "4_4") (pintype "passive"))
    )
    (net (code "89") (name "TIM3_CH1") (class "Default")
      (node (ref "IC1") (pin "37") (pinfunction "PC6/(TIM3_CH1)_37") (pintype "bidirectional"))
      (node (ref "R13") (pin "2") (pinfunction "2_2") (pintype "passive"))
    )
    (net (code "90") (name "TIM3_CH2") (class "Default")
      (node (ref "IC1") (pin "38") (pinfunction "PC7/(TIM3_CH2)_38") (pintype "bidirectional"))
      (node (ref "R14") (pin "2") (pinfunction "2_2") (pintype "passive"))
    )
    (net (code "91") (name "TIM3_CH3") (class "Default")
      (node (ref "IC1") (pin "39") (pinfunction "PC8/(TIM3_CH3)_39") (pintype "bidirectional"))
      (node (ref "R15") (pin "2") (pinfunction "2_2") (pintype "passive"))
    )
    (net (code "92") (name "TIM3_CH4") (class "Default")
      (node (ref "IC1") (pin "40") (pinfunction "PC9/(TIM3_CH4)_40") (pintype "bidirectional"))
      (node (ref "R16") (pin "2") (pinfunction "2_2") (pintype "passive"))
    )
    (net (code "93") (name "TIM4_CH1") (class "Default")
      (node (ref "IC1") (pin "58") (pinfunction "PB6/I2C1_SCL/TIM4_CH1/(USART1_TX)_58") (pintype "bidirectional"))
      (node (ref "R17") (pin "2") (pinfunction "2_2") (pintype "passive"))
    )
    (net (code "94") (name "TIM4_CH2") (class "Default")
      (node (ref "IC1") (pin "59") (pinfunction "PB7/I2C1_SDA/TIM4_CH2/(USART1_RX)_59") (pintype "bidirectional"))
      (node (ref "R18") (pin "2") (pinfunction "2_2") (pintype "passive"))
    )
    (net (code "95") (name "TIM4_CH3") (class "Default")
      (node (ref "IC1") (pin "61") (pinfunction "PB8/TIM4_CH3/(I2C1_SCL/CANRX)_61") (pintype "bidirectional"))
      (node (ref "R19") (pin "2") (pinfunction "2_2") (pintype "passive"))
    )
    (net (code "96") (name "TIM4_CH4") (class "Default")
      (node (ref "IC1") (pin "62") (pinfunction "PB9/TIM4_CH4/(I2C1_SDA/CANTX)_62") (pintype "bidirectional"))
      (node (ref "R20") (pin "2") (pinfunction "2_2") (pintype "passive"))
    )
    (net (code "97") (name "TXD1") (class "Default")
      (node (ref "IC1") (pin "42") (pinfunction "PA9/USART1_TX/TIM1_CH2_42") (pintype "bidirectional"))
      (node (ref "JP2") (pin "2") (pinfunction "2_2") (pintype "passive"))
    )
    (net (code "98") (name "TXD3") (class "Default")
      (node (ref "IC1") (pin "51") (pinfunction "PC10/(USART3_TX)_51") (pintype "bidirectional"))
      (node (ref "IC3") (pin "2") (pinfunction "RE/_2") (pintype "input"))
      (node (ref "IC3") (pin "3") (pinfunction "DE_3") (pintype "input"))
      (node (ref "R26") (pin "2") (pinfunction "2_2") (pintype "passive"))
    )
    (net (code "99") (name "VBAT") (class "Default")
      (node (ref "G1") (pin "+") (pinfunction "+_+") (pintype "passive"))
      (node (ref "IC1") (pin "1") (pinfunction "VBAT_1") (pintype "power_in"))
    )
    (net (code "100") (name "VDDA") (class "Default")
      (node (ref "C6") (pin "1") (pinfunction "1_1") (pintype "passive"))
      (node (ref "IC1") (pin "13") (pinfunction "VDDA_13") (pintype "power_in"))
      (node (ref "L1") (pin "2") (pinfunction "2_2") (pintype "passive"))
      (node (ref "SW3") (pin "1") (pinfunction "P_1") (pintype "passive"))
      (node (ref "SW4") (pin "1") (pinfunction "P_1") (pintype "passive"))
      (node (ref "SW5") (pin "1") (pinfunction "P_1") (pintype "passive"))
    )
    (net (code "101") (name "unconnected-(SWD1-Pad6)") (class "Default")
      (node (ref "SWD1") (pin "6") (pinfunction "6_6") (pintype "passive"))
    )
    (net (code "102") (name "unconnected-(U1-MASS-Pad4)") (class "Default")
      (node (ref "U1") (pin "4") (pinfunction "MASS_4") (pintype "passive"))
    )
    (net (code "103") (name "~{LCD_CS}") (class "Default")
      (node (ref "LCD1") (pin "2") (pinfunction "~{CS}_2") (pintype "input"))
      (node (ref "R41") (pin "1") (pinfunction "1_1") (pintype "passive"))
      (node (ref "R46") (pin "2") (pinfunction "2_2") (pintype "passive"))
    )
    (net (code "104") (name "~{RESET}") (class "Default")
      (node (ref "C5") (pin "1") (pinfunction "1_1") (pintype "passive"))
      (node (ref "IC1") (pin "7") (pinfunction "~{RESET}_7") (pintype "input"))
      (node (ref "LCD1") (pin "1") (pinfunction "~{RST}_1") (pintype "input"))
      (node (ref "R8") (pin "1") (pinfunction "1_1") (pintype "passive"))
      (node (ref "SW2") (pin "2") (pinfunction "S_2") (pintype "passive"))
      (node (ref "SWD1") (pin "5") (pinfunction "5_5") (pintype "passive"))
    )
  )
)
